# iRat_2_0.net
KiCad netlist of a schematic drawn in Altium Designer
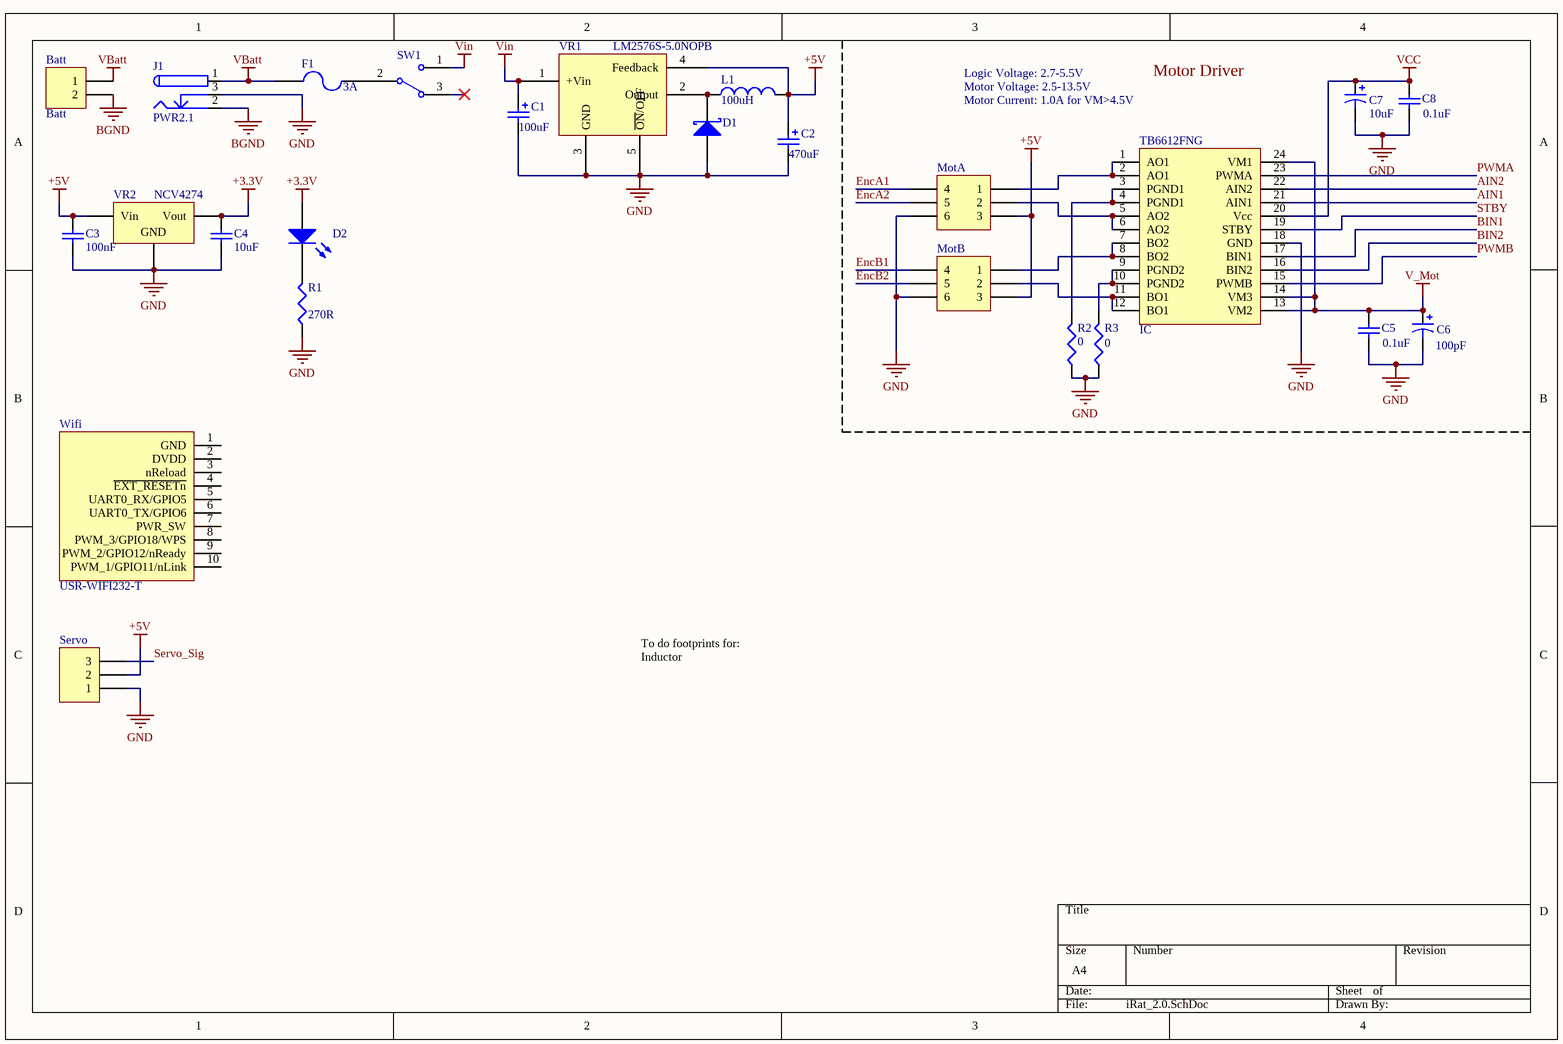
[diagram p0: iRat_2.0.SchDoc]

(export (version "E")
  (design (tool "Eeschema 10.0.6"))
  (components
    (comp (ref "Batt")
      (value "Batt")
      (footprint "Molex 43045-0202")
      (description "Header, 2-Pin")
      (fields (field (name "PUBLISHER") "Altium Limited"))
      (libsource (lib "Miscellaneous Connectors") (part "Header 2"))
    )
    (comp (ref "C1")
      (value "100uF")
      (footprint "Capacitor_SizeD8")
      (description "Polarized Capacitor (Radial)")
      (fields (field (name "Comment") "Cap Pol2") (field (name "PUBLISHER") "Altium Limited"))
      (libsource (lib "Miscellaneous Devices") (part "Cap Pol2"))
    )
    (comp (ref "C2")
      (value "470uF")
      (footprint "Capacitor - 8x10.5")
      (description "Polarized Capacitor (Radial)")
      (fields (field (name "Comment") "Cap Pol2") (field (name "PUBLISHER") "Altium Limited"))
      (libsource (lib "Miscellaneous Devices") (part "Cap Pol2"))
    )
    (comp (ref "C3")
      (value "100nF")
      (footprint "1608[0603]")
      (description "Capacitor (Semiconductor SIM Model)")
      (fields (field (name "Comment") "Cap Semi") (field (name "PUBLISHER") "Altium Limited"))
      (libsource (lib "Miscellaneous Devices") (part "Cap Semi"))
    )
    (comp (ref "C4")
      (value "10uF")
      (footprint "1608[0603]")
      (description "Capacitor (Semiconductor SIM Model)")
      (fields (field (name "Comment") "Cap Semi") (field (name "PUBLISHER") "Altium Limited"))
      (libsource (lib "Miscellaneous Devices") (part "Cap Semi"))
    )
    (comp (ref "C5")
      (value "0.1uF")
      (footprint "C1206")
      (description "Capacitor (Semiconductor SIM Model)")
      (fields (field (name "Comment") "Cap Semi") (field (name "PUBLISHER") "Altium Limited"))
      (libsource (lib "Miscellaneous Devices") (part "Cap Semi"))
    )
    (comp (ref "C6")
      (value "100pF")
      (footprint "C0805")
      (description "Polarized Capacitor (Surface Mount)")
      (fields (field (name "Comment") "Cap Pol3") (field (name "PUBLISHER") "Altium Limited"))
      (libsource (lib "Miscellaneous Devices") (part "Cap Pol3"))
    )
    (comp (ref "C7")
      (value "10uF")
      (footprint "C0805")
      (description "Polarized Capacitor (Surface Mount)")
      (fields (field (name "Comment") "Cap Pol3") (field (name "PUBLISHER") "Altium Limited"))
      (libsource (lib "Miscellaneous Devices") (part "Cap Pol3"))
    )
    (comp (ref "C8")
      (value "0.1uF")
      (footprint "C1206")
      (description "Capacitor (Semiconductor SIM Model)")
      (fields (field (name "Comment") "Cap Semi") (field (name "PUBLISHER") "Altium Limited"))
      (libsource (lib "Miscellaneous Devices") (part "Cap Semi"))
    )
    (comp (ref "D1")
      (value "D Schottky")
      (footprint "SMB")
      (description "Schottky Diode")
      (fields (field (name "PUBLISHER") "Altium Limited"))
      (libsource (lib "Miscellaneous Devices") (part "D Schottky"))
    )
    (comp (ref "D2")
      (value "LNJ347W83RA")
      (footprint "0402-A")
      (description "GREEN Power LED")
      (fields (field (name "PUBLISHER") "Altium Limited"))
      (libsource (lib "Miscellaneous Devices") (part "LED2"))
    )
    (comp (ref "F1")
      (value "3A")
      (footprint "1812")
      (description "Fuse")
      (fields (field (name "PUBLISHER") "Altium Limited"))
      (libsource (lib "Miscellaneous Devices") (part "Fuse 2"))
    )
    (comp (ref "J1")
      (value "PWR2.1")
      (footprint "DCP21")
      (description "Low Voltage Power Supply Connector")
      (fields (field (name "PUBLISHER") "Altium Limited"))
      (libsource (lib "Miscellaneous Connectors") (part "PWR2.5"))
    )
    (comp (ref "L1")
      (value "100uH")
      (footprint "0402-A")
      (description "Inductor")
      (fields (field (name "PUBLISHER") "Altium Limited"))
      (libsource (lib "Miscellaneous Devices") (part "Inductor"))
    )
    (comp (ref "MotA")
      (value "Header 3X2A")
      (footprint "HDR2X3_CEN")
      (description "Header, 3-Pin, Dual row")
      (fields (field (name "PUBLISHER") "Altium Limited"))
      (libsource (lib "Miscellaneous Connectors") (part "Header 3X2A"))
    )
    (comp (ref "MotB")
      (value "Header 3X2A")
      (footprint "HDR2X3_CEN")
      (description "Header, 3-Pin, Dual row")
      (fields (field (name "PUBLISHER") "Altium Limited"))
      (libsource (lib "Miscellaneous Connectors") (part "Header 3X2A"))
    )
    (comp (ref "R1")
      (value "270R")
      (footprint "0402")
      (description "Resistor")
      (fields (field (name "Comment") "Res3") (field (name "PUBLISHER") "Altium Limited"))
      (libsource (lib "Miscellaneous Devices") (part "Res3"))
    )
    (comp (ref "R2")
      (value "0")
      (footprint "J1-0603")
      (description "Resistor")
      (fields (field (name "Comment") "Shunt Resistor") (field (name "PUBLISHER") "Altium Limited"))
      (libsource (lib "Miscellaneous Devices") (part "Res3"))
    )
    (comp (ref "R3")
      (value "0")
      (footprint "J1-0603")
      (description "Resistor")
      (fields (field (name "Comment") "Shunt Resistor") (field (name "PUBLISHER") "Altium Limited"))
      (libsource (lib "Miscellaneous Devices") (part "Res3"))
    )
    (comp (ref "Servo")
      (value "Servo1")
      (footprint "HDR1X3")
      (description "Header, 3-Pin")
      (fields (field (name "PUBLISHER") "Altium Limited"))
      (libsource (lib "Miscellaneous Connectors") (part "Header 3"))
    )
    (comp (ref "SW1")
      (value "SW-SPDT")
      (footprint "Slide_Switch")
      (description "SPDT Subminiature Toggle Switch, Right Angle Mounting, Vertical Actuation")
      (fields (field (name "PUBLISHER") "Altium Limited"))
      (libsource (lib "Miscellaneous Devices") (part "SW-SPDT"))
    )
    (comp (ref "TB6612FNG")
      (value "IC")
      (description "Motor Driver IC")
      (libsource (lib "iRat") (part "TB6612FNG IC"))
    )
    (comp (ref "VR1")
      (value "LM2576S-5.0NOPB")
      (footprint "LM2576S")
      (description "5V Switching Regulator")
      (libsource (lib "iRat") (part "LM2576S-5.0NOPB"))
    )
    (comp (ref "VR2")
      (value "NCV4274")
      (footprint "SOT223_N")
      (description "Voltage Regulator")
      (fields (field (name "PUBLISHER") "Altium Limited"))
      (libsource (lib "Miscellaneous Devices") (part "Volt Reg"))
    )
    (comp (ref "Wifi")
      (value "USR-WIFI232-T")
      (footprint "USR-WIFI232-T")
      (libsource (lib "iRat") (part "USR-WIFI232-T"))
    )
  )
  (nets
    (net (code "1") (name "+3.3V") (class "Default")
      (node (ref "C4") (pin "2") (pinfunction "2_2") (pintype "passive"))
      (node (ref "D2") (pin "1") (pinfunction "A_1") (pintype "passive"))
      (node (ref "VR2") (pin "3") (pinfunction "Vout_3") (pintype "passive"))
    )
    (net (code "2") (name "+5V") (class "Default")
      (node (ref "C2") (pin "1") (pinfunction "1_1") (pintype "passive"))
      (node (ref "C3") (pin "2") (pinfunction "2_2") (pintype "passive"))
      (node (ref "L1") (pin "2") (pinfunction "2_2") (pintype "passive"))
      (node (ref "MotA") (pin "3") (pinfunction "3_3") (pintype "passive"))
      (node (ref "MotB") (pin "3") (pinfunction "3_3") (pintype "passive"))
      (node (ref "Servo") (pin "2") (pinfunction "2_2") (pintype "passive"))
      (node (ref "VR1") (pin "4") (pinfunction "Feedback_4") (pintype "passive"))
      (node (ref "VR2") (pin "1") (pinfunction "Vin_1") (pintype "passive"))
    )
    (net (code "3") (name "/AIN1") (class "Default")
      (node (ref "TB6612FNG") (pin "21") (pinfunction "AIN1_21") (pintype "passive"))
    )
    (net (code "4") (name "/AIN2") (class "Default")
      (node (ref "TB6612FNG") (pin "22") (pinfunction "AIN2_22") (pintype "passive"))
    )
    (net (code "5") (name "/BIN1") (class "Default")
      (node (ref "TB6612FNG") (pin "17") (pinfunction "BIN1_17") (pintype "passive"))
    )
    (net (code "6") (name "/BIN2") (class "Default")
      (node (ref "TB6612FNG") (pin "16") (pinfunction "BIN2_16") (pintype "passive"))
    )
    (net (code "7") (name "/EncA1") (class "Default")
      (node (ref "MotA") (pin "4") (pinfunction "4_4") (pintype "passive"))
    )
    (net (code "8") (name "/EncA2") (class "Default")
      (node (ref "MotA") (pin "5") (pinfunction "5_5") (pintype "passive"))
    )
    (net (code "9") (name "/EncB1") (class "Default")
      (node (ref "MotB") (pin "4") (pinfunction "4_4") (pintype "passive"))
    )
    (net (code "10") (name "/EncB2") (class "Default")
      (node (ref "MotB") (pin "5") (pinfunction "5_5") (pintype "passive"))
    )
    (net (code "11") (name "/PWMA") (class "Default")
      (node (ref "TB6612FNG") (pin "23") (pinfunction "PWMA_23") (pintype "passive"))
    )
    (net (code "12") (name "/PWMB") (class "Default")
      (node (ref "TB6612FNG") (pin "15") (pinfunction "PWMB_15") (pintype "passive"))
    )
    (net (code "13") (name "/STBY") (class "Default")
      (node (ref "TB6612FNG") (pin "19") (pinfunction "STBY_19") (pintype "passive"))
    )
    (net (code "14") (name "/Servo_Sig") (class "Default")
      (node (ref "Servo") (pin "3") (pinfunction "3_3") (pintype "passive"))
    )
    (net (code "15") (name "BGND") (class "Default")
      (node (ref "Batt") (pin "2") (pinfunction "2_2") (pintype "passive"))
      (node (ref "J1") (pin "2") (pinfunction "2_2") (pintype "power_in"))
    )
    (net (code "16") (name "GND") (class "Default")
      (node (ref "C1") (pin "2") (pinfunction "2_2") (pintype "passive"))
      (node (ref "C2") (pin "2") (pinfunction "2_2") (pintype "passive"))
      (node (ref "C3") (pin "1") (pinfunction "1_1") (pintype "passive"))
      (node (ref "C4") (pin "1") (pinfunction "1_1") (pintype "passive"))
      (node (ref "C5") (pin "2") (pinfunction "2_2") (pintype "passive"))
      (node (ref "C6") (pin "2") (pinfunction "2_2") (pintype "passive"))
      (node (ref "C7") (pin "2") (pinfunction "2_2") (pintype "passive"))
      (node (ref "C8") (pin "2") (pinfunction "2_2") (pintype "passive"))
      (node (ref "D1") (pin "1") (pinfunction "A_1") (pintype "passive"))
      (node (ref "J1") (pin "3") (pinfunction "3_3") (pintype "power_in"))
      (node (ref "MotA") (pin "6") (pinfunction "6_6") (pintype "passive"))
      (node (ref "MotB") (pin "6") (pinfunction "6_6") (pintype "passive"))
      (node (ref "R1") (pin "1") (pinfunction "1_1") (pintype "passive"))
      (node (ref "R2") (pin "1") (pinfunction "1_1") (pintype "passive"))
      (node (ref "R3") (pin "1") (pinfunction "1_1") (pintype "passive"))
      (node (ref "Servo") (pin "1") (pinfunction "1_1") (pintype "passive"))
      (node (ref "TB6612FNG") (pin "18") (pinfunction "GND_18") (pintype "passive"))
      (node (ref "VR1") (pin "3") (pinfunction "GND_3") (pintype "passive"))
      (node (ref "VR1") (pin "5") (pinfunction "~{ON}/OFF_5") (pintype "passive"))
      (node (ref "VR2") (pin "2") (pinfunction "GND_2") (pintype "passive"))
    )
    (net (code "17") (name "Net-(D1-K)") (class "Default")
      (node (ref "D1") (pin "2") (pinfunction "K_2") (pintype "passive"))
      (node (ref "L1") (pin "1") (pinfunction "1_1") (pintype "passive"))
      (node (ref "VR1") (pin "2") (pinfunction "Output_2") (pintype "passive"))
    )
    (net (code "18") (name "Net-(D2-K)") (class "Default")
      (node (ref "D2") (pin "2") (pinfunction "K_2") (pintype "passive"))
      (node (ref "R1") (pin "2") (pinfunction "2_2") (pintype "passive"))
    )
    (net (code "19") (name "Net-(F1-Pad2)") (class "Default")
      (node (ref "F1") (pin "2") (pinfunction "2_2") (pintype "passive"))
      (node (ref "SW1") (pin "2") (pinfunction "2_2") (pintype "passive"))
    )
    (net (code "20") (name "Net-(MotA-Pad1)") (class "Default")
      (node (ref "MotA") (pin "1") (pinfunction "1_1") (pintype "passive"))
      (node (ref "TB6612FNG") (pin "1") (pinfunction "AO1_1") (pintype "passive"))
      (node (ref "TB6612FNG") (pin "2") (pinfunction "AO1_2") (pintype "passive"))
    )
    (net (code "21") (name "Net-(MotA-Pad2)") (class "Default")
      (node (ref "MotA") (pin "2") (pinfunction "2_2") (pintype "passive"))
      (node (ref "TB6612FNG") (pin "5") (pinfunction "AO2_5") (pintype "passive"))
      (node (ref "TB6612FNG") (pin "6") (pinfunction "AO2_6") (pintype "passive"))
    )
    (net (code "22") (name "Net-(MotB-Pad1)") (class "Default")
      (node (ref "MotB") (pin "1") (pinfunction "1_1") (pintype "passive"))
      (node (ref "TB6612FNG") (pin "7") (pinfunction "BO2_7") (pintype "passive"))
      (node (ref "TB6612FNG") (pin "8") (pinfunction "BO2_8") (pintype "passive"))
    )
    (net (code "23") (name "Net-(MotB-Pad2)") (class "Default")
      (node (ref "MotB") (pin "2") (pinfunction "2_2") (pintype "passive"))
      (node (ref "TB6612FNG") (pin "11") (pinfunction "BO1_11") (pintype "passive"))
      (node (ref "TB6612FNG") (pin "12") (pinfunction "BO1_12") (pintype "passive"))
    )
    (net (code "24") (name "Net-(R2-Pad2)") (class "Default")
      (node (ref "R2") (pin "2") (pinfunction "2_2") (pintype "passive"))
      (node (ref "TB6612FNG") (pin "3") (pinfunction "PGND1_3") (pintype "passive"))
      (node (ref "TB6612FNG") (pin "4") (pinfunction "PGND1_4") (pintype "passive"))
    )
    (net (code "25") (name "Net-(R3-Pad2)") (class "Default")
      (node (ref "R3") (pin "2") (pinfunction "2_2") (pintype "passive"))
      (node (ref "TB6612FNG") (pin "10") (pinfunction "PGND2_10") (pintype "passive"))
      (node (ref "TB6612FNG") (pin "9") (pinfunction "PGND2_9") (pintype "passive"))
    )
    (net (code "26") (name "VBatt") (class "Default")
      (node (ref "Batt") (pin "1") (pinfunction "1_1") (pintype "passive"))
      (node (ref "F1") (pin "1") (pinfunction "1_1") (pintype "passive"))
      (node (ref "J1") (pin "1") (pinfunction "1_1") (pintype "power_in"))
    )
    (net (code "27") (name "VCC") (class "Default")
      (node (ref "C7") (pin "1") (pinfunction "1_1") (pintype "passive"))
      (node (ref "C8") (pin "1") (pinfunction "1_1") (pintype "passive"))
      (node (ref "TB6612FNG") (pin "20") (pinfunction "Vcc_20") (pintype "passive"))
    )
    (net (code "28") (name "V_Mot") (class "Default")
      (node (ref "C5") (pin "1") (pinfunction "1_1") (pintype "passive"))
      (node (ref "C6") (pin "1") (pinfunction "1_1") (pintype "passive"))
      (node (ref "TB6612FNG") (pin "13") (pinfunction "VM2_13") (pintype "passive"))
      (node (ref "TB6612FNG") (pin "14") (pinfunction "VM3_14") (pintype "passive"))
      (node (ref "TB6612FNG") (pin "24") (pinfunction "VM1_24") (pintype "passive"))
    )
    (net (code "29") (name "Vin") (class "Default")
      (node (ref "C1") (pin "1") (pinfunction "1_1") (pintype "passive"))
      (node (ref "SW1") (pin "1") (pinfunction "1_1") (pintype "passive"))
      (node (ref "VR1") (pin "1") (pinfunction "+Vin_1") (pintype "passive"))
    )
    (net (code "30") (name "unconnected-(SW1-Pad3)") (class "Default")
      (node (ref "SW1") (pin "3") (pinfunction "3_3") (pintype "passive+no_connect"))
    )
    (net (code "31") (name "unconnected-(VR2-GND-Pad4)") (class "Default")
      (node (ref "VR2") (pin "4") (pinfunction "GND_4") (pintype "passive"))
    )
    (net (code "32") (name "unconnected-(Wifi-DVDD-Pad2)") (class "Default")
      (node (ref "Wifi") (pin "2") (pinfunction "DVDD_2") (pintype "passive"))
    )
    (net (code "33") (name "unconnected-(Wifi-GND-Pad1)") (class "Default")
      (node (ref "Wifi") (pin "1") (pinfunction "GND_1") (pintype "passive"))
    )
    (net (code "34") (name "unconnected-(Wifi-PWM_1{slash}GPIO11{slash}nLink-Pad10)") (class "Default")
      (node (ref "Wifi") (pin "10") (pinfunction "PWM_1/GPIO11/nLink_10") (pintype "passive"))
    )
    (net (code "35") (name "unconnected-(Wifi-PWM_2{slash}GPIO12{slash}nReady-Pad9)") (class "Default")
      (node (ref "Wifi") (pin "9") (pinfunction "PWM_2/GPIO12/nReady_9") (pintype "passive"))
    )
    (net (code "36") (name "unconnected-(Wifi-PWM_3{slash}GPIO18{slash}WPS-Pad8)") (class "Default")
      (node (ref "Wifi") (pin "8") (pinfunction "PWM_3/GPIO18/WPS_8") (pintype "passive"))
    )
    (net (code "37") (name "unconnected-(Wifi-PWR_SW-Pad7)") (class "Default")
      (node (ref "Wifi") (pin "7") (pinfunction "PWR_SW_7") (pintype "passive"))
    )
    (net (code "38") (name "unconnected-(Wifi-UART0_RX{slash}GPIO5-Pad5)") (class "Default")
      (node (ref "Wifi") (pin "5") (pinfunction "UART0_RX/GPIO5_5") (pintype "passive"))
    )
    (net (code "39") (name "unconnected-(Wifi-UART0_TX{slash}GPIO6-Pad6)") (class "Default")
      (node (ref "Wifi") (pin "6") (pinfunction "UART0_TX/GPIO6_6") (pintype "passive"))
    )
    (net (code "40") (name "unconnected-(Wifi-nReload-Pad3)") (class "Default")
      (node (ref "Wifi") (pin "3") (pinfunction "nReload_3") (pintype "passive"))
    )
    (net (code "41") (name "unconnected-(Wifi-~{EXT_RESETn}-Pad4)") (class "Default")
      (node (ref "Wifi") (pin "4") (pinfunction "~{EXT_RESETn}_4") (pintype "passive"))
    )
  )
)
